# Power.net
KiCad netlist of a schematic drawn in Altium Designer
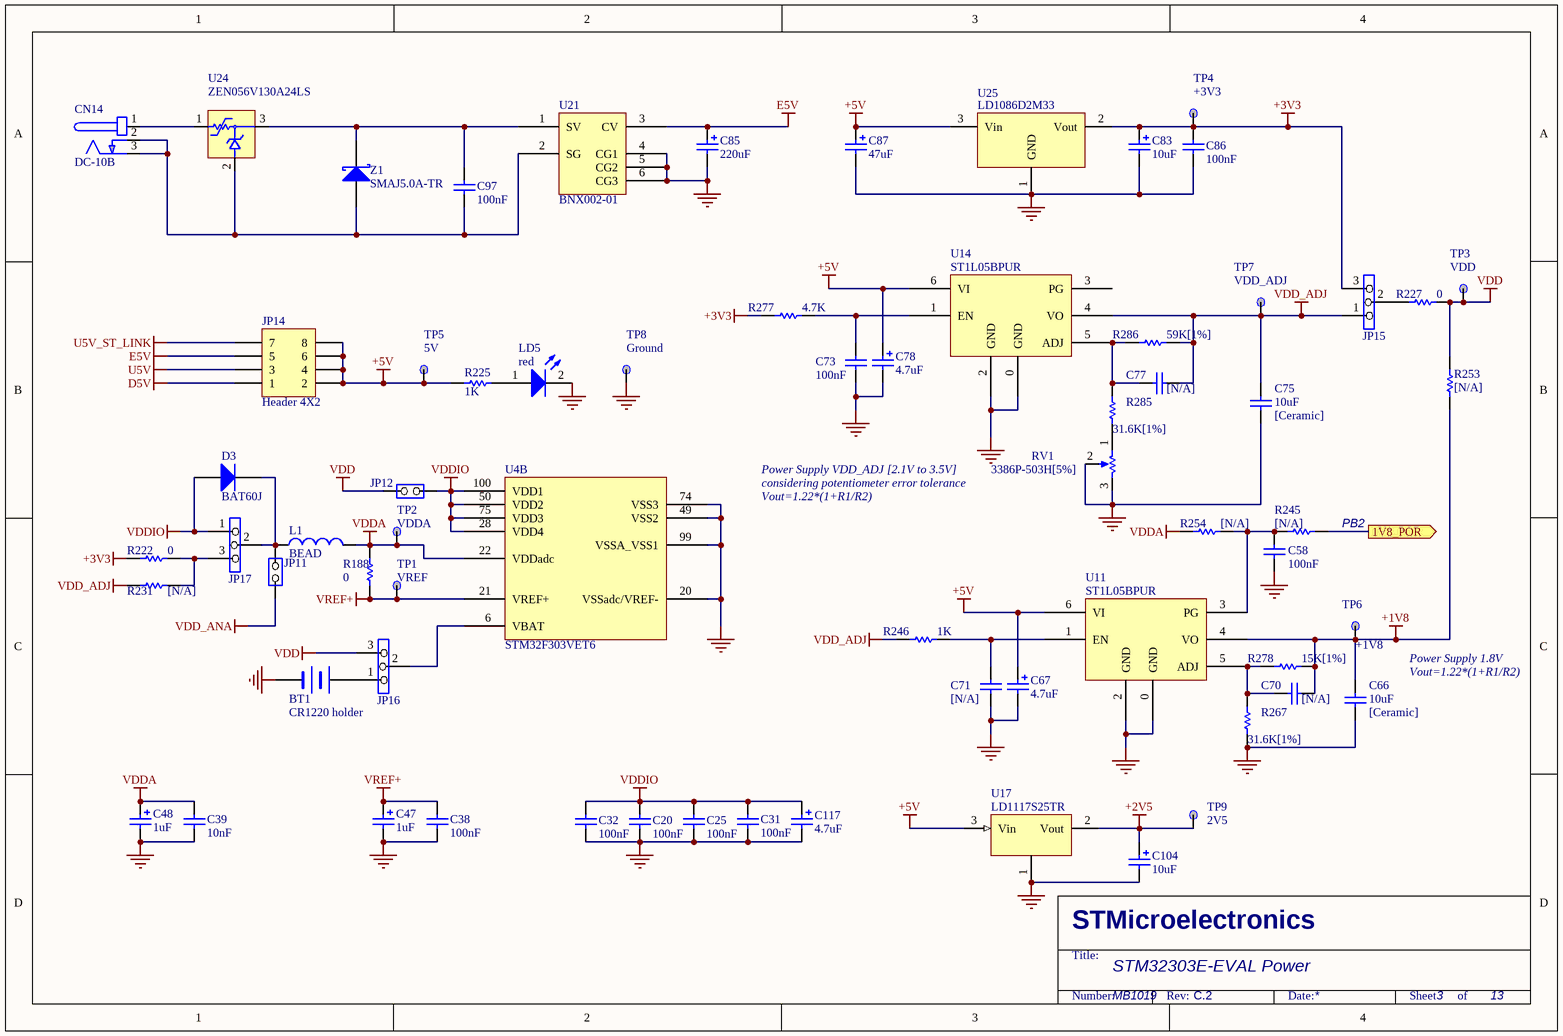
[diagram p0: Power.SchDoc]

(export (version "E")
  (design (tool "Eeschema 10.0.6"))
  (components
    (comp (ref "BT1")
      (value "CR1220 holder")
      (footprint "LI1220_1")
      (description "Battery")
      (libsource (lib "*") (part "BATTERY"))
    )
    (comp (ref "C20")
      (value "100nF")
      (footprint "0603C")
      (description "Capacitor")
      (fields (field (name "PUBLISHER") "Altium Limited"))
      (libsource (lib "Miscellaneous Devices") (part "CAP"))
    )
    (comp (ref "C25")
      (value "100nF")
      (footprint "0603C")
      (description "Capacitor")
      (fields (field (name "PUBLISHER") "Altium Limited"))
      (libsource (lib "Miscellaneous Devices") (part "CAP"))
    )
    (comp (ref "C31")
      (value "100nF")
      (footprint "0603C")
      (description "Capacitor")
      (fields (field (name "PUBLISHER") "Altium Limited"))
      (libsource (lib "Miscellaneous Devices") (part "Cap"))
    )
    (comp (ref "C32")
      (value "100nF")
      (footprint "0603C")
      (description "Capacitor")
      (fields (field (name "PUBLISHER") "Altium Limited"))
      (libsource (lib "Miscellaneous Devices") (part "CAP"))
    )
    (comp (ref "C38")
      (value "100nF")
      (footprint "0603C")
      (description "Capacitor")
      (fields (field (name "PUBLISHER") "Altium Limited"))
      (libsource (lib "Miscellaneous Devices") (part "Cap"))
    )
    (comp (ref "C39")
      (value "10nF")
      (footprint "0603C")
      (description "Capacitor")
      (fields (field (name "PUBLISHER") "Altium Limited"))
      (libsource (lib "Miscellaneous Devices") (part "Cap"))
    )
    (comp (ref "C47")
      (value "1uF")
      (footprint "TAN-A")
      (description "Polarized Capacitor (Radial)")
      (fields (field (name "PUBLISHER") "Altium Limited"))
      (libsource (lib "Miscellaneous Devices") (part "Cap Pol1"))
    )
    (comp (ref "C48")
      (value "1uF")
      (footprint "TAN-A")
      (description "Polarized Capacitor (Radial)")
      (fields (field (name "PUBLISHER") "Altium Limited"))
      (libsource (lib "Miscellaneous Devices") (part "Cap Pol1"))
    )
    (comp (ref "C58")
      (value "100nF")
      (footprint "0603C")
      (description "Capacitor")
      (fields (field (name "PUBLISHER") "Altium Limited"))
      (libsource (lib "Miscellaneous Devices") (part "Cap"))
    )
    (comp (ref "C66")
      (value "10uF")
      (footprint "0805C")
      (description "Capacitor")
      (fields (field (name "PUBLISHER") "Altium Limited"))
      (libsource (lib "Miscellaneous Devices") (part "Cap"))
    )
    (comp (ref "C67")
      (value "4.7uF")
      (footprint "TAN-A")
      (description "Polarized Capacitor (Radial)")
      (fields (field (name "PUBLISHER") "Altium Limited"))
      (libsource (lib "*") (part "Cap Pol1"))
    )
    (comp (ref "C70")
      (value "[N/A]")
      (footprint "0603C")
      (description "Capacitor")
      (fields (field (name "PUBLISHER") "Altium Limited"))
      (libsource (lib "Miscellaneous Devices") (part "Cap"))
    )
    (comp (ref "C71")
      (value "[N/A]")
      (footprint "0603C")
      (description "Capacitor")
      (fields (field (name "PUBLISHER") "Altium Limited"))
      (libsource (lib "Miscellaneous Devices") (part "Cap"))
    )
    (comp (ref "C73")
      (value "100nF")
      (footprint "0603C")
      (description "Capacitor")
      (fields (field (name "PUBLISHER") "Altium Limited"))
      (libsource (lib "Miscellaneous Devices") (part "Cap"))
    )
    (comp (ref "C75")
      (value "10uF")
      (footprint "0805C")
      (description "Capacitor")
      (fields (field (name "PUBLISHER") "Altium Limited"))
      (libsource (lib "Miscellaneous Devices") (part "Cap"))
    )
    (comp (ref "C77")
      (value "[N/A]")
      (footprint "0603C")
      (description "Capacitor")
      (fields (field (name "PUBLISHER") "Altium Limited"))
      (libsource (lib "Miscellaneous Devices") (part "Cap"))
    )
    (comp (ref "C78")
      (value "4.7uF")
      (footprint "TAN-A")
      (description "Polarized Capacitor (Radial)")
      (fields (field (name "PUBLISHER") "Altium Limited"))
      (libsource (lib "*") (part "Cap Pol1"))
    )
    (comp (ref "C83")
      (value "10uF")
      (footprint "TAN-A")
      (description "Polarized Capacitor (Radial)")
      (fields (field (name "PUBLISHER") "Altium Limited"))
      (libsource (lib "Miscellaneous Devices") (part "Cap Pol1"))
    )
    (comp (ref "C85")
      (value "220uF")
      (footprint "C310M")
      (description "Polarized Capacitor (Radial)")
      (fields (field (name "PUBLISHER") "Altium Limited"))
      (libsource (lib "Miscellaneous Devices") (part "Cap Pol1"))
    )
    (comp (ref "C86")
      (value "100nF")
      (footprint "0603C")
      (description "Capacitor")
      (fields (field (name "PUBLISHER") "Altium Limited"))
      (libsource (lib "Miscellaneous Devices") (part "Cap"))
    )
    (comp (ref "C87")
      (value "47uF")
      (footprint "C200M")
      (description "Polarized Capacitor (Radial)")
      (fields (field (name "PUBLISHER") "Altium Limited"))
      (libsource (lib "Miscellaneous Devices") (part "Cap Pol1"))
    )
    (comp (ref "C97")
      (value "100nF")
      (footprint "0603C")
      (description "Capacitor")
      (fields (field (name "PUBLISHER") "Altium Limited"))
      (libsource (lib "Miscellaneous Devices") (part "CAP"))
    )
    (comp (ref "C104")
      (value "10uF")
      (footprint "TAN-A")
      (description "Polarized Capacitor (Radial)")
      (fields (field (name "PUBLISHER") "Altium Limited"))
      (libsource (lib "Miscellaneous Devices") (part "Cap Pol1"))
    )
    (comp (ref "C117")
      (value "4.7uF")
      (footprint "TAN-A")
      (description "Polarized Capacitor (Radial)")
      (fields (field (name "PUBLISHER") "Altium Limited"))
      (libsource (lib "*") (part "Cap Pol1"))
    )
    (comp (ref "CN14") (value "DC-10B") (footprint "DC10B") (libsource (lib "STR910_SCHLIB") (part "PJ202A")))
    (comp (ref "D3")
      (value "BAT60J")
      (footprint "SOD-323")
      (description "Default Diode")
      (fields (field (name "PUBLISHER") "Altium Limited"))
      (libsource (lib "Miscellaneous Devices") (part "Diode"))
    )
    (comp (ref "JP11") (value "~") (footprint "SIP2") (libsource (lib "*") (part "JP2")))
    (comp (ref "JP12") (value "~") (footprint "SIP2") (libsource (lib "*") (part "JP2")))
    (comp (ref "JP14")
      (value "Header 4X2")
      (footprint "2*4P")
      (description "Header, 4-Pin, Dual row")
      (fields (field (name "PUBLISHER") "Altium Limited"))
      (libsource (lib "Miscellaneous Connectors") (part "Header 4X2"))
    )
    (comp (ref "JP15") (value "~") (footprint "SIP3") (libsource (lib "STR910_SCHLIB") (part "Jumper3")))
    (comp (ref "JP16") (value "~") (footprint "SIP3") (libsource (lib "") (part "Jumper3_1")))
    (comp (ref "JP17") (value "~") (footprint "SIP3") (libsource (lib "STR910_SCHLIB") (part "Jumper3")))
    (comp (ref "L1")
      (value "BEAD")
      (footprint "0603L")
      (description "Inductor")
      (fields (field (name "PUBLISHER") "Altium Limited"))
      (libsource (lib "Miscellaneous Devices") (part "Inductor"))
    )
    (comp (ref "LD5")
      (value "red")
      (footprint "0603D")
      (description "Typical RED, GREEN, YELLOW, AMBER GaAs LED")
      (fields (field (name "PUBLISHER") "Altium Limited"))
      (libsource (lib "Miscellaneous Devices") (part "LED2"))
    )
    (comp (ref "R188")
      (value "0")
      (footprint "0603R")
      (description "Resistor")
      (fields (field (name "PUBLISHER") "Altium Limited"))
      (libsource (lib "Miscellaneous Devices") (part "Res1"))
    )
    (comp (ref "R222")
      (value "0")
      (footprint "0603R")
      (description "Resistor")
      (fields (field (name "PUBLISHER") "Altium Limited"))
      (libsource (lib "Miscellaneous Devices") (part "Res1"))
    )
    (comp (ref "R225")
      (value "1K")
      (footprint "0603R")
      (description "Resistor")
      (fields (field (name "PUBLISHER") "Altium Limited"))
      (libsource (lib "Miscellaneous Devices") (part "res1"))
    )
    (comp (ref "R227")
      (value "0")
      (footprint "0603R")
      (description "Resistor")
      (fields (field (name "PUBLISHER") "Altium Limited"))
      (libsource (lib "Miscellaneous Devices") (part "Res1"))
    )
    (comp (ref "R231")
      (value "[N/A]")
      (footprint "0603R")
      (description "Resistor")
      (fields (field (name "PUBLISHER") "Altium Limited"))
      (libsource (lib "Miscellaneous Devices") (part "Res1"))
    )
    (comp (ref "R245")
      (value "[N/A]")
      (footprint "0603R")
      (description "Resistor")
      (fields (field (name "PUBLISHER") "Altium Limited"))
      (libsource (lib "Miscellaneous Devices") (part "Res1"))
    )
    (comp (ref "R246")
      (value "1K")
      (footprint "0603R")
      (description "Resistor")
      (fields (field (name "PUBLISHER") "Altium Limited"))
      (libsource (lib "Miscellaneous Devices") (part "res1"))
    )
    (comp (ref "R253")
      (value "[N/A]")
      (footprint "0603R")
      (description "Resistor")
      (fields (field (name "PUBLISHER") "Altium Limited"))
      (libsource (lib "Miscellaneous Devices") (part "Res1"))
    )
    (comp (ref "R254")
      (value "[N/A]")
      (footprint "0603R")
      (description "Resistor")
      (fields (field (name "PUBLISHER") "Altium Limited"))
      (libsource (lib "Miscellaneous Devices") (part "res1"))
    )
    (comp (ref "R267")
      (value "31.6K[1%]")
      (footprint "0603R")
      (description "Resistor")
      (fields (field (name "PUBLISHER") "Altium Limited"))
      (libsource (lib "Miscellaneous Devices") (part "Res1"))
    )
    (comp (ref "R277")
      (value "4.7K")
      (footprint "0603R")
      (description "Resistor")
      (fields (field (name "PUBLISHER") "Altium Limited"))
      (libsource (lib "Miscellaneous Devices") (part "res1"))
    )
    (comp (ref "R278")
      (value "15K[1%]")
      (footprint "0603R")
      (description "Resistor")
      (fields (field (name "PUBLISHER") "Altium Limited"))
      (libsource (lib "Miscellaneous Devices") (part "Res1"))
    )
    (comp (ref "R285")
      (value "31.6K[1%]")
      (footprint "0603R")
      (description "Resistor")
      (fields (field (name "PUBLISHER") "Altium Limited"))
      (libsource (lib "Miscellaneous Devices") (part "Res1"))
    )
    (comp (ref "R286")
      (value "59K[1%]")
      (footprint "0603R")
      (description "Resistor")
      (fields (field (name "PUBLISHER") "Altium Limited"))
      (libsource (lib "Miscellaneous Devices") (part "Res1"))
    )
    (comp (ref "RV1")
      (value "3386P-503H[5%]")
      (footprint "3296W")
      (libsource (lib "STR910_SCHLIB") (part "RV"))
    )
    (comp (ref "TP1") (value "VREF") (footprint "TP") (libsource (lib "*") (part "TP")))
    (comp (ref "TP2") (value "VDDA") (footprint "TP") (libsource (lib "*") (part "TP")))
    (comp (ref "TP3") (value "VDD") (footprint "TP") (libsource (lib "*") (part "TP")))
    (comp (ref "TP4") (value "+3V3") (footprint "TP") (libsource (lib "*") (part "TP")))
    (comp (ref "TP5") (value "5V") (footprint "TP") (libsource (lib "*") (part "TP")))
    (comp (ref "TP6") (value "+1V8") (footprint "TP") (libsource (lib "*") (part "TP")))
    (comp (ref "TP7") (value "VDD_ADJ") (footprint "TP") (libsource (lib "*") (part "TP")))
    (comp (ref "TP8") (value "Ground") (footprint "TP") (libsource (lib "*") (part "TP")))
    (comp (ref "TP9") (value "2V5") (footprint "TP") (libsource (lib "*") (part "TP")))
    (comp (ref "U4")
      (value "STM32F303VET6")
      (footprint "IC149-100-025-B5")
      (libsource (lib "MB1019") (part "STM32F303VCT6"))
    )
    (comp (ref "U11") (value "ST1L05BPUR") (footprint "DFN6(3X3)") (libsource (lib "*") (part "ST1L05")))
    (comp (ref "U14") (value "ST1L05BPUR") (footprint "DFN6(3X3)") (libsource (lib "*") (part "ST1L05")))
    (comp (ref "U17") (value "LD1117S25TR") (footprint "SOT-223") (libsource (lib "*") (part "LD1117")))
    (comp (ref "U21")
      (value "BNX002-01")
      (footprint "BNX001")
      (libsource (lib "STR910_SCHLIB") (part "BNX002"))
    )
    (comp (ref "U24")
      (value "ZEN056V130A24LS")
      (footprint "polyzen")
      (libsource (lib "STR910_SCHLIB") (part "ZEN056V130A24LS"))
    )
    (comp (ref "U25") (value "LD1086D2M33") (footprint "D2PAK/A") (libsource (lib "*") (part "VOLTREG1")))
    (comp (ref "Z1")
      (value "SMAJ5.0A-TR")
      (footprint "1R1C")
      (description "Schottky Diode")
      (fields (field (name "PUBLISHER") "Altium Limited"))
      (libsource (lib "Miscellaneous Devices") (part "D Schottky"))
    )
  )
  (nets
    (net (code "1") (name "+1V8") (class "Default")
      (node (ref "C66") (pin "1") (pinfunction "1_1") (pintype "passive"))
      (node (ref "C70") (pin "2") (pinfunction "2_2") (pintype "passive"))
      (node (ref "R253") (pin "2") (pinfunction "2_2") (pintype "passive"))
      (node (ref "R278") (pin "1") (pinfunction "1_1") (pintype "passive"))
      (node (ref "TP6") (pin "1") (pinfunction "1_1") (pintype "passive"))
      (node (ref "U11") (pin "4") (pinfunction "VO_4") (pintype "passive"))
    )
    (net (code "2") (name "+2V5") (class "Default")
      (node (ref "C104") (pin "1") (pinfunction "1_1") (pintype "passive"))
      (node (ref "TP9") (pin "1") (pinfunction "1_1") (pintype "passive"))
      (node (ref "U17") (pin "2") (pinfunction "Vout_2") (pintype "power_in"))
    )
    (net (code "3") (name "+3V3") (class "Default")
      (node (ref "C83") (pin "1") (pinfunction "1_1") (pintype "passive"))
      (node (ref "C86") (pin "1") (pinfunction "1_1") (pintype "passive"))
      (node (ref "JP15") (pin "3") (pintype "passive"))
      (node (ref "R222") (pin "2") (pinfunction "2_2") (pintype "passive"))
      (node (ref "R277") (pin "2") (pinfunction "2_2") (pintype "passive"))
      (node (ref "TP4") (pin "1") (pinfunction "1_1") (pintype "passive"))
      (node (ref "U25") (pin "2") (pinfunction "Vout_2") (pintype "passive"))
    )
    (net (code "4") (name "+5V") (class "Default")
      (node (ref "C67") (pin "1") (pinfunction "1_1") (pintype "passive"))
      (node (ref "C78") (pin "1") (pinfunction "1_1") (pintype "passive"))
      (node (ref "C87") (pin "1") (pinfunction "1_1") (pintype "passive"))
      (node (ref "JP14") (pin "2") (pinfunction "2_2") (pintype "passive"))
      (node (ref "JP14") (pin "4") (pinfunction "4_4") (pintype "passive"))
      (node (ref "JP14") (pin "6") (pinfunction "6_6") (pintype "passive"))
      (node (ref "JP14") (pin "8") (pinfunction "8_8") (pintype "passive"))
      (node (ref "R225") (pin "2") (pinfunction "2_2") (pintype "passive"))
      (node (ref "TP5") (pin "1") (pinfunction "1_1") (pintype "passive"))
      (node (ref "U11") (pin "6") (pinfunction "VI_6") (pintype "passive"))
      (node (ref "U14") (pin "6") (pinfunction "VI_6") (pintype "passive"))
      (node (ref "U17") (pin "3") (pinfunction "Vin_3") (pintype "input"))
      (node (ref "U25") (pin "3") (pinfunction "Vin_3") (pintype "passive"))
    )
    (net (code "5") (name "/1V8_POR") (class "Default")
      (node (ref "R245") (pin "1") (pinfunction "1_1") (pintype "passive"))
    )
    (net (code "6") (name "D5V") (class "Default")
      (node (ref "JP14") (pin "1") (pinfunction "1_1") (pintype "passive"))
    )
    (net (code "7") (name "E5V") (class "Default")
      (node (ref "C85") (pin "1") (pinfunction "1_1") (pintype "passive"))
      (node (ref "JP14") (pin "5") (pinfunction "5_5") (pintype "passive"))
      (node (ref "U21") (pin "3") (pinfunction "CV_3") (pintype "passive"))
    )
    (net (code "8") (name "GND") (class "Default")
      (node (ref "BT1") (pin "2") (pinfunction "-_2") (pintype "passive"))
      (node (ref "C104") (pin "2") (pinfunction "2_2") (pintype "passive"))
      (node (ref "C117") (pin "2") (pinfunction "2_2") (pintype "passive"))
      (node (ref "C20") (pin "2") (pinfunction "2_2") (pintype "passive"))
      (node (ref "C25") (pin "2") (pinfunction "2_2") (pintype "passive"))
      (node (ref "C31") (pin "1") (pinfunction "1_1") (pintype "passive"))
      (node (ref "C32") (pin "2") (pinfunction "2_2") (pintype "passive"))
      (node (ref "C38") (pin "1") (pinfunction "1_1") (pintype "passive"))
      (node (ref "C39") (pin "1") (pinfunction "1_1") (pintype "passive"))
      (node (ref "C47") (pin "2") (pinfunction "2_2") (pintype "passive"))
      (node (ref "C48") (pin "2") (pinfunction "2_2") (pintype "passive"))
      (node (ref "C58") (pin "2") (pinfunction "2_2") (pintype "passive"))
      (node (ref "C66") (pin "2") (pinfunction "2_2") (pintype "passive"))
      (node (ref "C67") (pin "2") (pinfunction "2_2") (pintype "passive"))
      (node (ref "C71") (pin "2") (pinfunction "2_2") (pintype "passive"))
      (node (ref "C73") (pin "2") (pinfunction "2_2") (pintype "passive"))
      (node (ref "C75") (pin "2") (pinfunction "2_2") (pintype "passive"))
      (node (ref "C78") (pin "2") (pinfunction "2_2") (pintype "passive"))
      (node (ref "C83") (pin "2") (pinfunction "2_2") (pintype "passive"))
      (node (ref "C85") (pin "2") (pinfunction "2_2") (pintype "passive"))
      (node (ref "C86") (pin "2") (pinfunction "2_2") (pintype "passive"))
      (node (ref "C87") (pin "2") (pinfunction "2_2") (pintype "passive"))
      (node (ref "LD5") (pin "2") (pinfunction "K_2") (pintype "passive"))
      (node (ref "R267") (pin "2") (pinfunction "2_2") (pintype "passive"))
      (node (ref "RV1") (pin "2") (pinfunction "TAP_2") (pintype "passive"))
      (node (ref "RV1") (pin "3") (pinfunction "TOP_3") (pintype "passive"))
      (node (ref "TP8") (pin "1") (pinfunction "1_1") (pintype "passive"))
      (node (ref "U11") (pin "0") (pinfunction "GND_0") (pintype "passive"))
      (node (ref "U11") (pin "2") (pinfunction "GND_2") (pintype "passive"))
      (node (ref "U14") (pin "0") (pinfunction "GND_0") (pintype "passive"))
      (node (ref "U14") (pin "2") (pinfunction "GND_2") (pintype "passive"))
      (node (ref "U17") (pin "1") (pintype "passive"))
      (node (ref "U21") (pin "4") (pinfunction "CG1_4") (pintype "passive"))
      (node (ref "U21") (pin "5") (pinfunction "CG2_5") (pintype "passive"))
      (node (ref "U21") (pin "6") (pinfunction "CG3_6") (pintype "passive"))
      (node (ref "U25") (pin "1") (pinfunction "GND_1") (pintype "passive"))
      (node (ref "U4") (pin "20") (pinfunction "VSSadc/VREF-_20") (pintype "passive"))
      (node (ref "U4") (pin "49") (pinfunction "VSS2_49") (pintype "passive"))
      (node (ref "U4") (pin "74") (pinfunction "VSS3_74") (pintype "passive"))
      (node (ref "U4") (pin "99") (pinfunction "VSSA_VSS1_99") (pintype "passive"))
    )
    (net (code "9") (name "Net-(BT1-+)") (class "Default")
      (node (ref "BT1") (pin "1") (pinfunction "+_1") (pintype "passive"))
      (node (ref "JP16") (pin "1") (pintype "passive"))
    )
    (net (code "10") (name "Net-(CN14-+)") (class "Default")
      (node (ref "CN14") (pin "1") (pinfunction "+_1") (pintype "passive"))
      (node (ref "U24") (pin "1") (pintype "passive"))
    )
    (net (code "11") (name "Net-(D3-K)") (class "Default")
      (node (ref "D3") (pin "2") (pinfunction "K_2") (pintype "passive"))
      (node (ref "JP11") (pin "2") (pinfunction "NO_2") (pintype "passive"))
      (node (ref "JP17") (pin "2") (pintype "passive"))
      (node (ref "L1") (pin "1") (pinfunction "1_1") (pintype "passive"))
    )
    (net (code "12") (name "Net-(JP15-Pad2)") (class "Default")
      (node (ref "JP15") (pin "2") (pintype "passive"))
      (node (ref "R227") (pin "2") (pinfunction "2_2") (pintype "passive"))
    )
    (net (code "13") (name "Net-(JP17-Pad3)") (class "Default")
      (node (ref "JP17") (pin "3") (pintype "passive"))
      (node (ref "R222") (pin "1") (pinfunction "1_1") (pintype "passive"))
      (node (ref "R231") (pin "1") (pinfunction "1_1") (pintype "passive"))
    )
    (net (code "14") (name "Net-(LD5-A)") (class "Default")
      (node (ref "LD5") (pin "1") (pinfunction "A_1") (pintype "passive"))
      (node (ref "R225") (pin "1") (pinfunction "1_1") (pintype "passive"))
    )
    (net (code "15") (name "Net-(RV1-BOT)") (class "Default")
      (node (ref "R285") (pin "2") (pinfunction "2_2") (pintype "passive"))
      (node (ref "RV1") (pin "1") (pinfunction "BOT_1") (pintype "passive"))
    )
    (net (code "16") (name "Net-(U4B-VBAT)") (class "Default")
      (node (ref "JP16") (pin "2") (pintype "passive"))
      (node (ref "U4") (pin "6") (pinfunction "VBAT_6") (pintype "passive"))
    )
    (net (code "17") (name "Net-(U11-ADJ)") (class "Default")
      (node (ref "C70") (pin "1") (pinfunction "1_1") (pintype "passive"))
      (node (ref "R267") (pin "1") (pinfunction "1_1") (pintype "passive"))
      (node (ref "R278") (pin "2") (pinfunction "2_2") (pintype "passive"))
      (node (ref "U11") (pin "5") (pinfunction "ADJ_5") (pintype "passive"))
    )
    (net (code "18") (name "Net-(U11-EN)") (class "Default")
      (node (ref "C71") (pin "1") (pinfunction "1_1") (pintype "passive"))
      (node (ref "R246") (pin "1") (pinfunction "1_1") (pintype "passive"))
      (node (ref "U11") (pin "1") (pinfunction "EN_1") (pintype "passive"))
    )
    (net (code "19") (name "Net-(U11-PG)") (class "Default")
      (node (ref "C58") (pin "1") (pinfunction "1_1") (pintype "passive"))
      (node (ref "R245") (pin "2") (pinfunction "2_2") (pintype "passive"))
      (node (ref "R254") (pin "2") (pinfunction "2_2") (pintype "passive"))
      (node (ref "U11") (pin "3") (pinfunction "PG_3") (pintype "passive"))
    )
    (net (code "20") (name "Net-(U14-ADJ)") (class "Default")
      (node (ref "C77") (pin "1") (pinfunction "1_1") (pintype "passive"))
      (node (ref "R285") (pin "1") (pinfunction "1_1") (pintype "passive"))
      (node (ref "R286") (pin "2") (pinfunction "2_2") (pintype "passive"))
      (node (ref "U14") (pin "5") (pinfunction "ADJ_5") (pintype "passive"))
    )
    (net (code "21") (name "Net-(U14-EN)") (class "Default")
      (node (ref "C73") (pin "1") (pinfunction "1_1") (pintype "passive"))
      (node (ref "R277") (pin "1") (pinfunction "1_1") (pintype "passive"))
      (node (ref "U14") (pin "1") (pinfunction "EN_1") (pintype "passive"))
    )
    (net (code "22") (name "Net-(U21-SG)") (class "Default")
      (node (ref "C97") (pin "2") (pinfunction "2_2") (pintype "passive"))
      (node (ref "CN14") (pin "2") (pinfunction "GND_2") (pintype "passive"))
      (node (ref "CN14") (pin "3") (pinfunction "GND_3") (pintype "passive"))
      (node (ref "U21") (pin "2") (pinfunction "SG_2") (pintype "passive"))
      (node (ref "U24") (pin "2") (pintype "passive"))
      (node (ref "Z1") (pin "1") (pinfunction "A_1") (pintype "passive"))
    )
    (net (code "23") (name "Net-(U21-SV)") (class "Default")
      (node (ref "C97") (pin "1") (pinfunction "1_1") (pintype "passive"))
      (node (ref "U21") (pin "1") (pinfunction "SV_1") (pintype "passive"))
      (node (ref "U24") (pin "3") (pintype "passive"))
      (node (ref "Z1") (pin "2") (pinfunction "K_2") (pintype "passive"))
    )
    (net (code "24") (name "U5V") (class "Default")
      (node (ref "JP14") (pin "3") (pinfunction "3_3") (pintype "passive"))
    )
    (net (code "25") (name "U5V_ST_LINK") (class "Default")
      (node (ref "JP14") (pin "7") (pinfunction "7_7") (pintype "passive"))
    )
    (net (code "26") (name "VDD") (class "Default")
      (node (ref "JP12") (pin "2") (pinfunction "NO_2") (pintype "passive"))
      (node (ref "JP16") (pin "3") (pintype "passive"))
      (node (ref "R227") (pin "1") (pinfunction "1_1") (pintype "passive"))
      (node (ref "R253") (pin "1") (pinfunction "1_1") (pintype "passive"))
      (node (ref "TP3") (pin "1") (pinfunction "1_1") (pintype "passive"))
    )
    (net (code "27") (name "VDDA") (class "Default")
      (node (ref "C39") (pin "2") (pinfunction "2_2") (pintype "passive"))
      (node (ref "C48") (pin "1") (pinfunction "1_1") (pintype "passive"))
      (node (ref "L1") (pin "2") (pinfunction "2_2") (pintype "passive"))
      (node (ref "R188") (pin "1") (pinfunction "1_1") (pintype "passive"))
      (node (ref "R254") (pin "1") (pinfunction "1_1") (pintype "passive"))
      (node (ref "TP2") (pin "1") (pinfunction "1_1") (pintype "passive"))
      (node (ref "U4") (pin "22") (pinfunction "VDDadc_22") (pintype "passive"))
    )
    (net (code "28") (name "VDDIO") (class "Default")
      (node (ref "C117") (pin "1") (pinfunction "1_1") (pintype "passive"))
      (node (ref "C20") (pin "1") (pinfunction "1_1") (pintype "passive"))
      (node (ref "C25") (pin "1") (pinfunction "1_1") (pintype "passive"))
      (node (ref "C31") (pin "2") (pinfunction "2_2") (pintype "passive"))
      (node (ref "C32") (pin "1") (pinfunction "1_1") (pintype "passive"))
      (node (ref "D3") (pin "1") (pinfunction "A_1") (pintype "passive"))
      (node (ref "JP12") (pin "1") (pinfunction "COMMON_1") (pintype "passive"))
      (node (ref "JP17") (pin "1") (pintype "passive"))
      (node (ref "U4") (pin "100") (pinfunction "VDD1_100") (pintype "passive"))
      (node (ref "U4") (pin "28") (pinfunction "VDD4_28") (pintype "passive"))
      (node (ref "U4") (pin "50") (pinfunction "VDD2_50") (pintype "passive"))
      (node (ref "U4") (pin "75") (pinfunction "VDD3_75") (pintype "passive"))
    )
    (net (code "29") (name "VDD_ADJ") (class "Default")
      (node (ref "C75") (pin "1") (pinfunction "1_1") (pintype "passive"))
      (node (ref "C77") (pin "2") (pinfunction "2_2") (pintype "passive"))
      (node (ref "JP15") (pin "1") (pintype "passive"))
      (node (ref "R231") (pin "2") (pinfunction "2_2") (pintype "passive"))
      (node (ref "R246") (pin "2") (pinfunction "2_2") (pintype "passive"))
      (node (ref "R286") (pin "1") (pinfunction "1_1") (pintype "passive"))
      (node (ref "TP7") (pin "1") (pinfunction "1_1") (pintype "passive"))
      (node (ref "U14") (pin "4") (pinfunction "VO_4") (pintype "passive"))
    )
    (net (code "30") (name "VDD_ANA") (class "Default")
      (node (ref "JP11") (pin "1") (pinfunction "COMMON_1") (pintype "passive"))
    )
    (net (code "31") (name "VREF+") (class "Default")
      (node (ref "C38") (pin "2") (pinfunction "2_2") (pintype "passive"))
      (node (ref "C47") (pin "1") (pinfunction "1_1") (pintype "passive"))
      (node (ref "R188") (pin "2") (pinfunction "2_2") (pintype "passive"))
      (node (ref "TP1") (pin "1") (pinfunction "1_1") (pintype "passive"))
      (node (ref "U4") (pin "21") (pinfunction "VREF+_21") (pintype "passive"))
    )
    (net (code "32") (name "unconnected-(U14-PG-Pad3)") (class "Default")
      (node (ref "U14") (pin "3") (pinfunction "PG_3") (pintype "passive"))
    )
  )
)
